# Boost_Converter_Schematic.net
KiCad netlist of a schematic drawn in Altium Designer
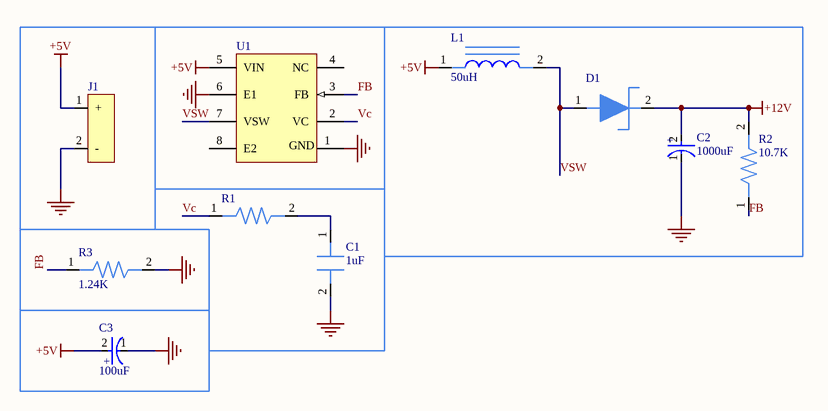
[diagram p0: Boost Converter Schematic.SchDoc]

(export (version "E")
  (design (tool "Eeschema 10.0.6"))
  (components
    (comp (ref "C1")
      (value "1uF")
      (footprint "C1210C105K5RACTU")
      (description "Ceramic Capacitor 1uF")
      (fields
        (field (name "MANUFACTURER") "KEMET")
        (field (name "MANUFACTURER PART NUMBER") "ESL105M100AC3AA")
      )
      (libsource (lib "Boost") (part "CL10B105KA8NNNC"))
    )
    (comp (ref "C2")
      (value "1000uF")
      (footprint "25PX1000MEFCT810X16")
      (fields
        (field (name "MANUFACTURER") "Rubycon")
        (field (name "MANUFACTURER PART NUMBER") "16ZLH1000MEFC10X16")
      )
      (libsource (lib "Boost") (part "16ZLH1000MEFC10X16"))
    )
    (comp (ref "C3")
      (value "100uF")
      (footprint "35ZLH100MEFC6.3X11")
      (description "CAP ALUM 100UF 20% 35V RADIAL")
      (fields (field (name "VOLTAGE") "35V") (field (name "TOLERANCE") "20%"))
      (libsource (lib "Boost") (part "a00bbbee19879c290e62620ae7e47b1"))
    )
    (comp (ref "D1")
      (value "BAT1000-7-F")
      (footprint "BAT1000-7-F")
      (description "Diode 40 V 1A Surface Mount SOT-23-3")
      (fields (field (name "MANUFACTURER") "Diodes"))
      (libsource (lib "Boost") (part "BAT1000-7-F"))
    )
    (comp (ref "J1") (value "0022013037") (libsource (lib "Boost") (part "Molex Connector")))
    (comp (ref "L1")
      (value "50uH")
      (footprint "CTX50-1-52-R")
      (description "General Purpose Inductor, 50uH, 1 Element, Iron-Core")
      (fields
        (field (name "MANUFACTURER") "Eaton Cooper")
        (field (name "MANUFACTURER PART NUMBER") "CTX50-1-52-R")
      )
      (libsource (lib "Boost") (part "CTX50-1-52-R"))
    )
    (comp (ref "R1")
      (value "~")
      (footprint "RC0805FR-071KL")
      (description "Fixed Resistor, Carbon Film, 0.25W, 1000ohm, 350V, 5% +/-Tol, -400,0ppm/Cel, Through Hole Mount")
      (fields
        (field (name "MANUFACTURER") "Stackpole Electronics")
        (field (name "MANUFACTURER PART NUMBER") "CF14JT1K00")
      )
      (libsource (lib "Boost") (part "RC0805FR-071KL"))
    )
    (comp (ref "R2")
      (value "10.7K")
      (footprint "RC0805FR-0710K7L")
      (description "Fixed Resistor, Metal Film, 0.25W, 10700ohm, 250V, 1% +/-Tol, -100,100ppm/Cel")
      (fields
        (field (name "MANUFACTURER") "Yageo")
        (field (name "MANUFACTURER PART NUMBER") "MFR-25FBF52-10K7")
      )
      (libsource (lib "Boost") (part "RC0805FR-0710K7L"))
    )
    (comp (ref "R3")
      (value "1.24K")
      (footprint "RC0805FR-071K24L")
      (description "Fixed Resistor, Metal Film, 0.25W, 1240ohm, 250V, 1% +/-Tol, -100,100ppm/Cel")
      (fields
        (field (name "MANUFACTURER") "Yageo")
        (field (name "MANUFACTURER PART NUMBER") "MFR-25FBF52-1K24")
      )
      (libsource (lib "Boost") (part "RC0805FR-071K24L"))
    )
    (comp (ref "U1")
      (value "LT1172CN8#PBF")
      (footprint "LT1172CN8#PBF-ND")
      (description "100 kHz, 1.25 A, High Efficiency Switching Regulator, 8-pin DIP (N8-8), 0 to 100 degC, Pb-Free")
      (fields (field (name "MANUFACTURER") "Linear Technology"))
      (libsource (lib "Boost") (part "LT-LT1172-X8-8"))
    )
  )
  (nets
    (net (code "1") (name "+5V") (class "Default")
      (node (ref "C3") (pin "2") (pinfunction "A_2") (pintype "passive"))
      (node (ref "J1") (pin "1") (pinfunction "+_1") (pintype "passive"))
      (node (ref "L1") (pin "1") (pinfunction "1_1") (pintype "passive"))
      (node (ref "U1") (pin "5") (pinfunction "VIN_5") (pintype "power_in"))
    )
    (net (code "2") (name "+12V") (class "Default")
      (node (ref "C2") (pin "2") (pinfunction "A_2") (pintype "passive"))
      (node (ref "D1") (pin "2") (pinfunction "2_2") (pintype "passive"))
      (node (ref "R2") (pin "2") (pinfunction "2_2") (pintype "passive"))
    )
    (net (code "3") (name "/FB") (class "Default")
      (node (ref "R2") (pin "1") (pinfunction "1_1") (pintype "passive"))
      (node (ref "R3") (pin "1") (pinfunction "1_1") (pintype "passive"))
      (node (ref "U1") (pin "3") (pinfunction "FB_3") (pintype "input"))
    )
    (net (code "4") (name "/VSW") (class "Default")
      (node (ref "D1") (pin "1") (pinfunction "1_1") (pintype "passive"))
      (node (ref "L1") (pin "2") (pinfunction "2_2") (pintype "passive"))
      (node (ref "U1") (pin "7") (pinfunction "VSW_7") (pintype "power_in"))
    )
    (net (code "5") (name "/Vc") (class "Default")
      (node (ref "R1") (pin "1") (pinfunction "1_1") (pintype "passive"))
      (node (ref "U1") (pin "2") (pinfunction "VC_2") (pintype "passive"))
    )
    (net (code "6") (name "GND") (class "Default")
      (node (ref "C1") (pin "2") (pinfunction "2_2") (pintype "passive"))
      (node (ref "C2") (pin "1") (pinfunction "C_1") (pintype "passive"))
      (node (ref "C3") (pin "1") (pinfunction "C_1") (pintype "passive"))
      (node (ref "J1") (pin "2") (pinfunction "-_2") (pintype "passive"))
      (node (ref "R3") (pin "2") (pinfunction "2_2") (pintype "passive"))
      (node (ref "U1") (pin "6") (pinfunction "E1_6") (pintype "passive"))
    )
    (net (code "7") (name "Net-(C1-Pad1)") (class "Default")
      (node (ref "C1") (pin "1") (pinfunction "1_1") (pintype "passive"))
      (node (ref "R1") (pin "2") (pinfunction "2_2") (pintype "passive"))
    )
    (net (code "8") (name "unconnected-(U1-E2-Pad8)") (class "Default")
      (node (ref "U1") (pin "8") (pinfunction "E2_8") (pintype "passive"))
    )
    (net (code "9") (name "unconnected-(U1-GND-Pad1)") (class "Default")
      (node (ref "U1") (pin "1") (pinfunction "GND_1") (pintype "power_in"))
    )
    (net (code "10") (name "unconnected-(U1-NC-Pad4)") (class "Default")
      (node (ref "U1") (pin "4") (pinfunction "NC_4") (pintype "passive"))
    )
  )
)
